# Digital_Output.net
KiCad netlist of a schematic drawn in Altium Designer
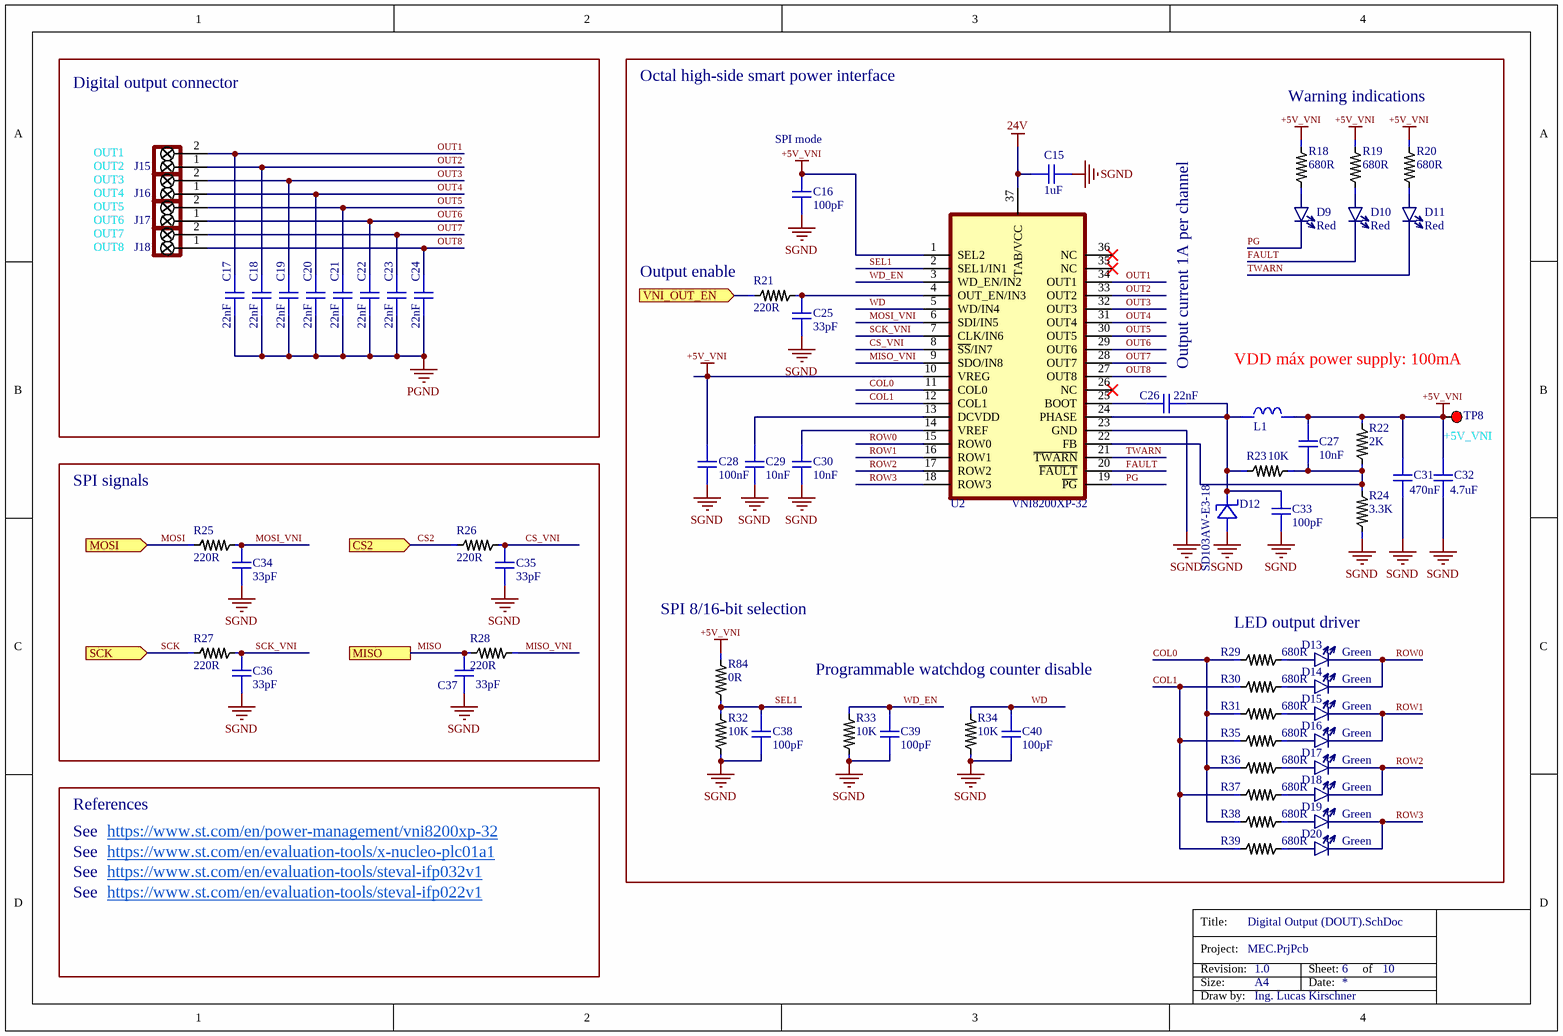
[diagram p0: Digital Output (DOUT).SchDoc]

(export (version "E")
  (design (tool "Eeschema 10.0.6"))
  (components
    (comp (ref "C15")
      (value "1uF")
      (footprint "CAPC1005N")
      (description "Multilayer Ceramic Capacitors MLCC - SMD/SMT 50V 1uF X5R 0402 10% HI CV")
      (fields (field (name "PART NUMBER") "CC0402KRX5R9BB105") (field (name "MANUFACTURER") "YAGEO"))
      (libsource (lib "SchLib") (part "C-MLCC-1uF-50V-10%-0402"))
    )
    (comp (ref "C16")
      (value "100pF")
      (footprint "CAPC1005N")
      (description "Multilayer Ceramic Capacitors MLCC - SMD/SMT 50 V 100pF X7R 0402 10%")
      (fields (field (name "PART NUMBER") "CC0402KRX7R9BB101") (field (name "MANUFACTURER") "YAGEO"))
      (libsource (lib "SchLib") (part "C-MLCC-100pF-50V-10%-0402"))
    )
    (comp (ref "C17")
      (value "22nF")
      (footprint "CAPC2012N")
      (description "Multilayer Ceramic Capacitors MLCC - SMD/SMT 100 V 0.022 uF X7R 0805 10%")
      (fields (field (name "PART NUMBER") "CC0805KRX7R0BB223") (field (name "MANUFACTURER") "YAGEO"))
      (libsource (lib "SchLib") (part "C-MLCC-22nF-100V-10%-0805"))
    )
    (comp (ref "C18")
      (value "22nF")
      (footprint "CAPC2012N")
      (description "Multilayer Ceramic Capacitors MLCC - SMD/SMT 100 V 0.022 uF X7R 0805 10%")
      (fields (field (name "PART NUMBER") "CC0805KRX7R0BB223") (field (name "MANUFACTURER") "YAGEO"))
      (libsource (lib "SchLib") (part "C-MLCC-22nF-100V-10%-0805"))
    )
    (comp (ref "C19")
      (value "22nF")
      (footprint "CAPC2012N")
      (description "Multilayer Ceramic Capacitors MLCC - SMD/SMT 100 V 0.022 uF X7R 0805 10%")
      (fields (field (name "PART NUMBER") "CC0805KRX7R0BB223") (field (name "MANUFACTURER") "YAGEO"))
      (libsource (lib "SchLib") (part "C-MLCC-22nF-100V-10%-0805"))
    )
    (comp (ref "C20")
      (value "22nF")
      (footprint "CAPC2012N")
      (description "Multilayer Ceramic Capacitors MLCC - SMD/SMT 100 V 0.022 uF X7R 0805 10%")
      (fields (field (name "PART NUMBER") "CC0805KRX7R0BB223") (field (name "MANUFACTURER") "YAGEO"))
      (libsource (lib "SchLib") (part "C-MLCC-22nF-100V-10%-0805"))
    )
    (comp (ref "C21")
      (value "22nF")
      (footprint "CAPC2012N")
      (description "Multilayer Ceramic Capacitors MLCC - SMD/SMT 100 V 0.022 uF X7R 0805 10%")
      (fields (field (name "PART NUMBER") "CC0805KRX7R0BB223") (field (name "MANUFACTURER") "YAGEO"))
      (libsource (lib "SchLib") (part "C-MLCC-22nF-100V-10%-0805"))
    )
    (comp (ref "C22")
      (value "22nF")
      (footprint "CAPC2012N")
      (description "Multilayer Ceramic Capacitors MLCC - SMD/SMT 100 V 0.022 uF X7R 0805 10%")
      (fields (field (name "PART NUMBER") "CC0805KRX7R0BB223") (field (name "MANUFACTURER") "YAGEO"))
      (libsource (lib "SchLib") (part "C-MLCC-22nF-100V-10%-0805"))
    )
    (comp (ref "C23")
      (value "22nF")
      (footprint "CAPC2012N")
      (description "Multilayer Ceramic Capacitors MLCC - SMD/SMT 100 V 0.022 uF X7R 0805 10%")
      (fields (field (name "PART NUMBER") "CC0805KRX7R0BB223") (field (name "MANUFACTURER") "YAGEO"))
      (libsource (lib "SchLib") (part "C-MLCC-22nF-100V-10%-0805"))
    )
    (comp (ref "C24")
      (value "22nF")
      (footprint "CAPC2012N")
      (description "Multilayer Ceramic Capacitors MLCC - SMD/SMT 100 V 0.022 uF X7R 0805 10%")
      (fields (field (name "PART NUMBER") "CC0805KRX7R0BB223") (field (name "MANUFACTURER") "YAGEO"))
      (libsource (lib "SchLib") (part "C-MLCC-22nF-100V-10%-0805"))
    )
    (comp (ref "C25")
      (value "33pF")
      (footprint "CAPC1005N")
      (description "Multilayer Ceramic Capacitors MLCC - SMD/SMT 50 V 33 pF C0G 0402 1%")
      (fields (field (name "PART NUMBER") "CC0402KRNPO9BN330") (field (name "MANUFACTURER") "YAGEO"))
      (libsource (lib "SchLib") (part "C-MLCC-33pF-50V-10%-0402"))
    )
    (comp (ref "C26")
      (value "22nF")
      (footprint "CAPC1005N")
      (description "Multilayer Ceramic Capacitors MLCC - SMD/SMT 50 V 0.022uF X7R 0402 10%")
      (fields (field (name "PART NUMBER") "CC0402KRX7R9BB223") (field (name "MANUFACTURER") "YAGEO"))
      (libsource (lib "SchLib") (part "C-MLCC-22nF-50V-10%-0402"))
    )
    (comp (ref "C27")
      (value "10nF")
      (footprint "CAPC1005N")
      (description "Multilayer Ceramic Capacitors MLCC - SMD/SMT 50 V 0.01uF X7R 0402 10%")
      (fields (field (name "PART NUMBER") "CC0402KRX7R9BB103") (field (name "MANUFACTURER") "YAGEO"))
      (libsource (lib "SchLib") (part "C-MLCC-10nF-50V-10%-0402"))
    )
    (comp (ref "C28")
      (value "100nF")
      (footprint "CAPC1005N")
      (description "Multilayer Ceramic Capacitors MLCC - SMD/SMT 50 V 0.1uF X7R 0402 10%")
      (fields (field (name "PART NUMBER") "CC0402KRX5R9BB104") (field (name "MANUFACTURER") "YAGEO"))
      (libsource (lib "SchLib") (part "C-MLCC-100nF-50V-10%-0402"))
    )
    (comp (ref "C29")
      (value "10nF")
      (footprint "CAPC1005N")
      (description "Multilayer Ceramic Capacitors MLCC - SMD/SMT 50 V 0.01uF X7R 0402 10%")
      (fields (field (name "PART NUMBER") "CC0402KRX7R9BB103") (field (name "MANUFACTURER") "YAGEO"))
      (libsource (lib "SchLib") (part "C-MLCC-10nF-50V-10%-0402"))
    )
    (comp (ref "C30")
      (value "10nF")
      (footprint "CAPC1005N")
      (description "Multilayer Ceramic Capacitors MLCC - SMD/SMT 50 V 0.01uF X7R 0402 10%")
      (fields (field (name "PART NUMBER") "CC0402KRX7R9BB103") (field (name "MANUFACTURER") "YAGEO"))
      (libsource (lib "SchLib") (part "C-MLCC-10nF-50V-10%-0402"))
    )
    (comp (ref "C31")
      (value "470nF")
      (footprint "CAPC1005N")
      (description "Multilayer Ceramic Capacitors MLCC - SMD/SMT 50 V 0.470uF X7R 0402 10%")
      (fields (field (name "PART NUMBER") "CC0402KRX5R9BB474") (field (name "MANUFACTURER") "YAGEO"))
      (libsource (lib "SchLib") (part "C-MLCC-470nF-50V-10%-0402"))
    )
    (comp (ref "C32")
      (value "4.7uF")
      (footprint "CAPC1005N")
      (description "Multilayer Ceramic Capacitors MLCC - SMD/SMT 10V 4.7uF X5R 0402 10% HI CV")
      (fields (field (name "PART NUMBER") "CC0402KRX5R6BB475") (field (name "MANUFACTURER") "YAGEO"))
      (libsource (lib "SchLib") (part "C-MLCC-4.7uF-10V-10%-0402"))
    )
    (comp (ref "C33")
      (value "100pF")
      (footprint "CAPC1005N")
      (description "Multilayer Ceramic Capacitors MLCC - SMD/SMT 50 V 100pF X7R 0402 10%")
      (fields (field (name "PART NUMBER") "CC0402KRX7R9BB101") (field (name "MANUFACTURER") "YAGEO"))
      (libsource (lib "SchLib") (part "C-MLCC-100pF-50V-10%-0402"))
    )
    (comp (ref "C34")
      (value "33pF")
      (footprint "CAPC1005N")
      (description "Multilayer Ceramic Capacitors MLCC - SMD/SMT 50 V 33 pF C0G 0402 1%")
      (fields (field (name "PART NUMBER") "CC0402KRNPO9BN330") (field (name "MANUFACTURER") "YAGEO"))
      (libsource (lib "SchLib") (part "C-MLCC-33pF-50V-10%-0402"))
    )
    (comp (ref "C35")
      (value "33pF")
      (footprint "CAPC1005N")
      (description "Multilayer Ceramic Capacitors MLCC - SMD/SMT 50 V 33 pF C0G 0402 1%")
      (fields (field (name "PART NUMBER") "CC0402KRNPO9BN330") (field (name "MANUFACTURER") "YAGEO"))
      (libsource (lib "SchLib") (part "C-MLCC-33pF-50V-10%-0402"))
    )
    (comp (ref "C36")
      (value "33pF")
      (footprint "CAPC1005N")
      (description "Multilayer Ceramic Capacitors MLCC - SMD/SMT 50 V 33 pF C0G 0402 1%")
      (fields (field (name "PART NUMBER") "CC0402KRNPO9BN330") (field (name "MANUFACTURER") "YAGEO"))
      (libsource (lib "SchLib") (part "C-MLCC-33pF-50V-10%-0402"))
    )
    (comp (ref "C37")
      (value "33pF")
      (footprint "CAPC1005N")
      (description "Multilayer Ceramic Capacitors MLCC - SMD/SMT 50 V 33 pF C0G 0402 1%")
      (fields (field (name "PART NUMBER") "CC0402KRNPO9BN330") (field (name "MANUFACTURER") "YAGEO"))
      (libsource (lib "SchLib") (part "C-MLCC-33pF-50V-10%-0402"))
    )
    (comp (ref "C38")
      (value "100pF")
      (footprint "CAPC1005N")
      (description "Multilayer Ceramic Capacitors MLCC - SMD/SMT 50 V 100pF X7R 0402 10%")
      (fields (field (name "PART NUMBER") "CC0402KRX7R9BB101") (field (name "MANUFACTURER") "YAGEO"))
      (libsource (lib "SchLib") (part "C-MLCC-100pF-50V-10%-0402"))
    )
    (comp (ref "C39")
      (value "100pF")
      (footprint "CAPC1005N")
      (description "Multilayer Ceramic Capacitors MLCC - SMD/SMT 50 V 100pF X7R 0402 10%")
      (fields (field (name "PART NUMBER") "CC0402KRX7R9BB101") (field (name "MANUFACTURER") "YAGEO"))
      (libsource (lib "SchLib") (part "C-MLCC-100pF-50V-10%-0402"))
    )
    (comp (ref "C40")
      (value "100pF")
      (footprint "CAPC1005N")
      (description "Multilayer Ceramic Capacitors MLCC - SMD/SMT 50 V 100pF X7R 0402 10%")
      (fields (field (name "PART NUMBER") "CC0402KRX7R9BB101") (field (name "MANUFACTURER") "YAGEO"))
      (libsource (lib "SchLib") (part "C-MLCC-100pF-50V-10%-0402"))
    )
    (comp (ref "D9")
      (value "Red")
      (footprint "LEDC1608X80N_RED")
      (description "Standard Single Color LEDs 0603 Red")
      (fields (field (name "PART NUMBER") "LTST-C190KRKT") (field (name "MANUFACTURER") "LITEON"))
      (libsource (lib "SchLib") (part "D-LED-RED-2V-20mA-0603"))
    )
    (comp (ref "D10")
      (value "Red")
      (footprint "LEDC1608X80N_RED")
      (description "Standard Single Color LEDs 0603 Red")
      (fields (field (name "PART NUMBER") "LTST-C190KRKT") (field (name "MANUFACTURER") "LITEON"))
      (libsource (lib "SchLib") (part "D-LED-RED-2V-20mA-0603"))
    )
    (comp (ref "D11")
      (value "Red")
      (footprint "LEDC1608X80N_RED")
      (description "Standard Single Color LEDs 0603 Red")
      (fields (field (name "PART NUMBER") "LTST-C190KRKT") (field (name "MANUFACTURER") "LITEON"))
      (libsource (lib "SchLib") (part "D-LED-RED-2V-20mA-0603"))
    )
    (comp (ref "D12")
      (value "Schottky Diodes")
      (footprint "SOD3705X110-2N")
      (description "Schottky Diodes & Rectifiers 350mA 40V SOD123")
      (fields
        (field (name "MANUFACTURER") "Vishay Semiconductors")
        (field (name "MOUSER PART #") "78-SD103AW-E3-18")
        (field (name "PART NUMBER") "SD103AW-E3-18")
      )
      (libsource (lib "SchLib") (part "D-SCH-350mA-40V-SOD123"))
    )
    (comp (ref "D13")
      (value "Green")
      (footprint "LEDC1608X80N_GREEN")
      (description "Standard Single Color LEDs 0603 Green")
      (fields (field (name "PART NUMBER") "LTST-C190KGKT") (field (name "MANUFACTURER") "LITEON"))
      (libsource (lib "SchLib") (part "D-LED-GREEN-2V-20mA-0603"))
    )
    (comp (ref "D14")
      (value "Green")
      (footprint "LEDC1608X80N_GREEN")
      (description "Standard Single Color LEDs 0603 Green")
      (fields (field (name "PART NUMBER") "LTST-C190KGKT") (field (name "MANUFACTURER") "LITEON"))
      (libsource (lib "SchLib") (part "D-LED-GREEN-2V-20mA-0603"))
    )
    (comp (ref "D15")
      (value "Green")
      (footprint "LEDC1608X80N_GREEN")
      (description "Standard Single Color LEDs 0603 Green")
      (fields (field (name "PART NUMBER") "LTST-C190KGKT") (field (name "MANUFACTURER") "LITEON"))
      (libsource (lib "SchLib") (part "D-LED-GREEN-2V-20mA-0603"))
    )
    (comp (ref "D16")
      (value "Green")
      (footprint "LEDC1608X80N_GREEN")
      (description "Standard Single Color LEDs 0603 Green")
      (fields (field (name "PART NUMBER") "LTST-C190KGKT") (field (name "MANUFACTURER") "LITEON"))
      (libsource (lib "SchLib") (part "D-LED-GREEN-2V-20mA-0603"))
    )
    (comp (ref "D17")
      (value "Green")
      (footprint "LEDC1608X80N_GREEN")
      (description "Standard Single Color LEDs 0603 Green")
      (fields (field (name "PART NUMBER") "LTST-C190KGKT") (field (name "MANUFACTURER") "LITEON"))
      (libsource (lib "SchLib") (part "D-LED-GREEN-2V-20mA-0603"))
    )
    (comp (ref "D18")
      (value "Green")
      (footprint "LEDC1608X80N_GREEN")
      (description "Standard Single Color LEDs 0603 Green")
      (fields (field (name "PART NUMBER") "LTST-C190KGKT") (field (name "MANUFACTURER") "LITEON"))
      (libsource (lib "SchLib") (part "D-LED-GREEN-2V-20mA-0603"))
    )
    (comp (ref "D19")
      (value "Green")
      (footprint "LEDC1608X80N_GREEN")
      (description "Standard Single Color LEDs 0603 Green")
      (fields (field (name "PART NUMBER") "LTST-C190KGKT") (field (name "MANUFACTURER") "LITEON"))
      (libsource (lib "SchLib") (part "D-LED-GREEN-2V-20mA-0603"))
    )
    (comp (ref "D20")
      (value "Green")
      (footprint "LEDC1608X80N_GREEN")
      (description "Standard Single Color LEDs 0603 Green")
      (fields (field (name "PART NUMBER") "LTST-C190KGKT") (field (name "MANUFACTURER") "LITEON"))
      (libsource (lib "SchLib") (part "D-LED-GREEN-2V-20mA-0603"))
    )
    (comp (ref "J15")
      (value "Terminal Blocks")
      (footprint "CONB_FIX508P-2N")
      (description "Pluggable Terminal Blocks 2 Pos 5.08mm pitch Through Hole Header")
      (fields (field (name "MOUSER PART #") "737-EBA-02-D-BU-01") (field (name "MANUFACTURER") "Adam Tech"))
      (libsource (lib "SchLib") (part "J-02-5P08-TERM-F-VERT-TH"))
    )
    (comp (ref "J16")
      (value "Terminal Blocks")
      (footprint "CONB_FIX508P-2N")
      (description "Pluggable Terminal Blocks 2 Pos 5.08mm pitch Through Hole Header")
      (fields (field (name "MOUSER PART #") "737-EBA-02-D-BU-01") (field (name "MANUFACTURER") "Adam Tech"))
      (libsource (lib "SchLib") (part "J-02-5P08-TERM-F-VERT-TH"))
    )
    (comp (ref "J17")
      (value "Terminal Blocks")
      (footprint "CONB_FIX508P-2N")
      (description "Pluggable Terminal Blocks 2 Pos 5.08mm pitch Through Hole Header")
      (fields (field (name "MOUSER PART #") "737-EBA-02-D-BU-01") (field (name "MANUFACTURER") "Adam Tech"))
      (libsource (lib "SchLib") (part "J-02-5P08-TERM-F-VERT-TH"))
    )
    (comp (ref "J18")
      (value "Terminal Blocks")
      (footprint "CONB_FIX508P-2N")
      (description "Pluggable Terminal Blocks 2 Pos 5.08mm pitch Through Hole Header")
      (fields (field (name "MOUSER PART #") "737-EBA-02-D-BU-01") (field (name "MANUFACTURER") "Adam Tech"))
      (libsource (lib "SchLib") (part "J-02-5P08-TERM-F-VERT-TH"))
    )
    (comp (ref "L1")
      (value "Power Inductor")
      (footprint "INDP4018220N")
      (description "Power Inductors - SMD 100uH 0.42A 1.6Ohms")
      (fields (field (name "MANUFACTURER") "Bourns") (field (name "PART NUMBER") "SRN4018-101M"))
      (libsource (lib "SchLib") (part "L-PWR-100uH-0.42A-SMT"))
    )
    (comp (ref "R18")
      (value "680R")
      (footprint "RESC1005N")
      (description "Thick Film Resistors - SMD General Purpose Chip Resistor 0402, 680Ohms, 1%, 1/16W")
      (fields (field (name "PART NUMBER") "RC0402FR-07680RL") (field (name "MANUFACTURER") "YAGEO"))
      (libsource (lib "SchLib") (part "R-THICK-680R-62.5mW-1%-0402"))
    )
    (comp (ref "R19")
      (value "680R")
      (footprint "RESC1005N")
      (description "Thick Film Resistors - SMD General Purpose Chip Resistor 0402, 680Ohms, 1%, 1/16W")
      (fields (field (name "PART NUMBER") "RC0402FR-07680RL") (field (name "MANUFACTURER") "YAGEO"))
      (libsource (lib "SchLib") (part "R-THICK-680R-62.5mW-1%-0402"))
    )
    (comp (ref "R20")
      (value "680R")
      (footprint "RESC1005N")
      (description "Thick Film Resistors - SMD General Purpose Chip Resistor 0402, 680Ohms, 1%, 1/16W")
      (fields (field (name "PART NUMBER") "RC0402FR-07680RL") (field (name "MANUFACTURER") "YAGEO"))
      (libsource (lib "SchLib") (part "R-THICK-680R-62.5mW-1%-0402"))
    )
    (comp (ref "R21")
      (value "220R")
      (footprint "RESC1005N")
      (description "Thick Film Resistors - SMD General Purpose Chip Resistor 0402, 220Ohms, 1%, 1/16W")
      (fields (field (name "PART NUMBER") "RC0402FR-07220RL") (field (name "MANUFACTURER") "YAGEO"))
      (libsource (lib "SchLib") (part "R-THICK-220R-62.5mW-1%-0402"))
    )
    (comp (ref "R22")
      (value "2K")
      (footprint "RESC1608N")
      (description "Thick Film Resistors - SMD General Purpose Chip Resistor 0603, 2kOhms, 1%, 1/10W")
      (fields (field (name "PART NUMBER") "RC0603FR-072KL") (field (name "MANUFACTURER") "YAGEO"))
      (libsource (lib "SchLib") (part "R-THICK-2K-100mW-1%-0603"))
    )
    (comp (ref "R23")
      (value "10K")
      (footprint "RESC1608N")
      (description "Thick Film Resistors - SMD General Purpose Chip Resistor 0603, 10kOhms, 1%, 1/10W")
      (fields (field (name "PART NUMBER") "RC0603FR-0710KL") (field (name "MANUFACTURER") "YAGEO"))
      (libsource (lib "SchLib") (part "R-THICK-10K-100mW-1%-0603"))
    )
    (comp (ref "R24")
      (value "3.3K")
      (footprint "RESC1608N")
      (description "Thick Film Resistors - SMD General Purpose Chip Resistor 0603, 3.3kOhms, 1%, 1/10W")
      (fields (field (name "PART NUMBER") "RC0603FR-073K3L") (field (name "MANUFACTURER") "YAGEO"))
      (libsource (lib "SchLib") (part "R-THICK-3K3-100mW-1%-0603"))
    )
    (comp (ref "R25")
      (value "220R")
      (footprint "RESC1005N")
      (description "Thick Film Resistors - SMD General Purpose Chip Resistor 0402, 220Ohms, 1%, 1/16W")
      (fields (field (name "PART NUMBER") "RC0402FR-07220RL") (field (name "MANUFACTURER") "YAGEO"))
      (libsource (lib "SchLib") (part "R-THICK-220R-62.5mW-1%-0402"))
    )
    (comp (ref "R26")
      (value "220R")
      (footprint "RESC1005N")
      (description "Thick Film Resistors - SMD General Purpose Chip Resistor 0402, 220Ohms, 1%, 1/16W")
      (fields (field (name "PART NUMBER") "RC0402FR-07220RL") (field (name "MANUFACTURER") "YAGEO"))
      (libsource (lib "SchLib") (part "R-THICK-220R-62.5mW-1%-0402"))
    )
    (comp (ref "R27")
      (value "220R")
      (footprint "RESC1005N")
      (description "Thick Film Resistors - SMD General Purpose Chip Resistor 0402, 220Ohms, 1%, 1/16W")
      (fields (field (name "PART NUMBER") "RC0402FR-07220RL") (field (name "MANUFACTURER") "YAGEO"))
      (libsource (lib "SchLib") (part "R-THICK-220R-62.5mW-1%-0402"))
    )
    (comp (ref "R28")
      (value "220R")
      (footprint "RESC1005N")
      (description "Thick Film Resistors - SMD General Purpose Chip Resistor 0402, 220Ohms, 1%, 1/16W")
      (fields (field (name "PART NUMBER") "RC0402FR-07220RL") (field (name "MANUFACTURER") "YAGEO"))
      (libsource (lib "SchLib") (part "R-THICK-220R-62.5mW-1%-0402"))
    )
    (comp (ref "R29")
      (value "680R")
      (footprint "RESC1005N")
      (description "Thick Film Resistors - SMD General Purpose Chip Resistor 0402, 680Ohms, 1%, 1/16W")
      (fields (field (name "PART NUMBER") "RC0402FR-07680RL") (field (name "MANUFACTURER") "YAGEO"))
      (libsource (lib "SchLib") (part "R-THICK-680R-62.5mW-1%-0402"))
    )
    (comp (ref "R30")
      (value "680R")
      (footprint "RESC1005N")
      (description "Thick Film Resistors - SMD General Purpose Chip Resistor 0402, 680Ohms, 1%, 1/16W")
      (fields (field (name "PART NUMBER") "RC0402FR-07680RL") (field (name "MANUFACTURER") "YAGEO"))
      (libsource (lib "SchLib") (part "R-THICK-680R-62.5mW-1%-0402"))
    )
    (comp (ref "R31")
      (value "680R")
      (footprint "RESC1005N")
      (description "Thick Film Resistors - SMD General Purpose Chip Resistor 0402, 680Ohms, 1%, 1/16W")
      (fields (field (name "PART NUMBER") "RC0402FR-07680RL") (field (name "MANUFACTURER") "YAGEO"))
      (libsource (lib "SchLib") (part "R-THICK-680R-62.5mW-1%-0402"))
    )
    (comp (ref "R32")
      (value "10K")
      (footprint "RESC1005N")
      (description "Thick Film Resistors - SMD General Purpose Chip Resistor 0402, 10kOhms, 1%, 1/16W")
      (fields (field (name "PART NUMBER") "RC0402FR-0710KL") (field (name "MANUFACTURER") "YAGEO"))
      (libsource (lib "SchLib") (part "R-THICK-10K-62.5mW-1%-0402"))
    )
    (comp (ref "R33")
      (value "10K")
      (footprint "RESC1005N")
      (description "Thick Film Resistors - SMD General Purpose Chip Resistor 0402, 10kOhms, 1%, 1/16W")
      (fields (field (name "PART NUMBER") "RC0402FR-0710KL") (field (name "MANUFACTURER") "YAGEO"))
      (libsource (lib "SchLib") (part "R-THICK-10K-62.5mW-1%-0402"))
    )
    (comp (ref "R34")
      (value "10K")
      (footprint "RESC1005N")
      (description "Thick Film Resistors - SMD General Purpose Chip Resistor 0402, 10kOhms, 1%, 1/16W")
      (fields (field (name "PART NUMBER") "RC0402FR-0710KL") (field (name "MANUFACTURER") "YAGEO"))
      (libsource (lib "SchLib") (part "R-THICK-10K-62.5mW-1%-0402"))
    )
    (comp (ref "R35")
      (value "680R")
      (footprint "RESC1005N")
      (description "Thick Film Resistors - SMD General Purpose Chip Resistor 0402, 680Ohms, 1%, 1/16W")
      (fields (field (name "PART NUMBER") "RC0402FR-07680RL") (field (name "MANUFACTURER") "YAGEO"))
      (libsource (lib "SchLib") (part "R-THICK-680R-62.5mW-1%-0402"))
    )
    (comp (ref "R36")
      (value "680R")
      (footprint "RESC1005N")
      (description "Thick Film Resistors - SMD General Purpose Chip Resistor 0402, 680Ohms, 1%, 1/16W")
      (fields (field (name "PART NUMBER") "RC0402FR-07680RL") (field (name "MANUFACTURER") "YAGEO"))
      (libsource (lib "SchLib") (part "R-THICK-680R-62.5mW-1%-0402"))
    )
    (comp (ref "R37")
      (value "680R")
      (footprint "RESC1005N")
      (description "Thick Film Resistors - SMD General Purpose Chip Resistor 0402, 680Ohms, 1%, 1/16W")
      (fields (field (name "PART NUMBER") "RC0402FR-07680RL") (field (name "MANUFACTURER") "YAGEO"))
      (libsource (lib "SchLib") (part "R-THICK-680R-62.5mW-1%-0402"))
    )
    (comp (ref "R38")
      (value "680R")
      (footprint "RESC1005N")
      (description "Thick Film Resistors - SMD General Purpose Chip Resistor 0402, 680Ohms, 1%, 1/16W")
      (fields (field (name "PART NUMBER") "RC0402FR-07680RL") (field (name "MANUFACTURER") "YAGEO"))
      (libsource (lib "SchLib") (part "R-THICK-680R-62.5mW-1%-0402"))
    )
    (comp (ref "R39")
      (value "680R")
      (footprint "RESC1005N")
      (description "Thick Film Resistors - SMD General Purpose Chip Resistor 0402, 680Ohms, 1%, 1/16W")
      (fields (field (name "PART NUMBER") "RC0402FR-07680RL") (field (name "MANUFACTURER") "YAGEO"))
      (libsource (lib "SchLib") (part "R-THICK-680R-62.5mW-1%-0402"))
    )
    (comp (ref "R84")
      (value "0R")
      (footprint "RESC1005N")
      (description "Thick Film Resistors - SMD General Purpose Chip Resistor 0402, 0Ohms, 1%, 1/16W")
      (fields (field (name "PART NUMBER") "RC0402FR-070RL") (field (name "MANUFACTURER") "YAGEO"))
      (libsource (lib "SchLib") (part "R-THICK-0R-62.5mW-1%-0402"))
    )
    (comp (ref "TP8")
      (value "Test point")
      (footprint "TP-1MM")
      (description "Test point, 1mm, exposed pad")
      (fields (field (name "JLCPCB PART #") "C5199810"))
      (libsource (lib "SchLib") (part "TP-1MM-SMD"))
    )
    (comp (ref "U2")
      (value "Power Switch ICs")
      (footprint "SOP50P1030X245-37N")
      (description "Power Switch ICs - Power Distribution 8-Ch Octal HS SSR 100mA VIPower")
      (fields
        (field (name "MANUFACTURER") "STMicroelectronics")
        (field (name "MOUSER PART #") "511-VNI8200XP-32")
        (field (name "PART NUMBER") "VNI8200XP-32")
      )
      (libsource (lib "SchLib") (part "U-VNI8200XP-32"))
    )
  )
  (nets
    (net (code "1") (name "+5V_VNI") (class "Default")
      (node (ref "C16") (pin "1") (pinfunction "1_1") (pintype "passive"))
      (node (ref "C27") (pin "1") (pinfunction "1_1") (pintype "passive"))
      (node (ref "C28") (pin "1") (pinfunction "1_1") (pintype "passive"))
      (node (ref "C31") (pin "1") (pinfunction "1_1") (pintype "passive"))
      (node (ref "C32") (pin "1") (pinfunction "1_1") (pintype "passive"))
      (node (ref "L1") (pin "2") (pinfunction "2_2") (pintype "passive"))
      (node (ref "R18") (pin "2") (pinfunction "2_2") (pintype "passive"))
      (node (ref "R19") (pin "2") (pinfunction "2_2") (pintype "passive"))
      (node (ref "R20") (pin "2") (pinfunction "2_2") (pintype "passive"))
      (node (ref "R22") (pin "2") (pinfunction "2_2") (pintype "passive"))
      (node (ref "R84") (pin "2") (pinfunction "2_2") (pintype "passive"))
      (node (ref "TP8") (pin "1") (pinfunction "1_1") (pintype "passive"))
      (node (ref "U2") (pin "1") (pinfunction "SEL2_1") (pintype "passive"))
      (node (ref "U2") (pin "10") (pinfunction "VREG_10") (pintype "passive"))
    )
    (net (code "2") (name "/COL0") (class "Default")
      (node (ref "R29") (pin "2") (pinfunction "2_2") (pintype "passive"))
      (node (ref "R31") (pin "2") (pinfunction "2_2") (pintype "passive"))
      (node (ref "R36") (pin "2") (pinfunction "2_2") (pintype "passive"))
      (node (ref "R38") (pin "2") (pinfunction "2_2") (pintype "passive"))
      (node (ref "U2") (pin "11") (pinfunction "COL0_11") (pintype "passive"))
    )
    (net (code "3") (name "/COL1") (class "Default")
      (node (ref "R30") (pin "2") (pinfunction "2_2") (pintype "passive"))
      (node (ref "R35") (pin "2") (pinfunction "2_2") (pintype "passive"))
      (node (ref "R37") (pin "2") (pinfunction "2_2") (pintype "passive"))
      (node (ref "R39") (pin "2") (pinfunction "2_2") (pintype "passive"))
      (node (ref "U2") (pin "12") (pinfunction "COL1_12") (pintype "passive"))
    )
    (net (code "4") (name "/CS2") (class "Default")
      (node (ref "R26") (pin "1") (pinfunction "1_1") (pintype "passive"))
    )
    (net (code "5") (name "/CS_VNI") (class "Default")
      (node (ref "C35") (pin "1") (pinfunction "1_1") (pintype "passive"))
      (node (ref "R26") (pin "2") (pinfunction "2_2") (pintype "passive"))
      (node (ref "U2") (pin "8") (pinfunction "~{SS}/IN7_8") (pintype "passive"))
    )
    (net (code "6") (name "/FAULT") (class "Default")
      (node (ref "D10") (pin "C") (pinfunction "C_C") (pintype "passive"))
      (node (ref "U2") (pin "20") (pinfunction "~{FAULT}_20") (pintype "passive"))
    )
    (net (code "7") (name "/MISO") (class "Default")
      (node (ref "C37") (pin "1") (pinfunction "1_1") (pintype "passive"))
      (node (ref "R28") (pin "1") (pinfunction "1_1") (pintype "passive"))
    )
    (net (code "8") (name "/MISO_VNI") (class "Default")
      (node (ref "R28") (pin "2") (pinfunction "2_2") (pintype "passive"))
      (node (ref "U2") (pin "9") (pinfunction "SDO/IN8_9") (pintype "passive"))
    )
    (net (code "9") (name "/MOSI") (class "Default")
      (node (ref "R25") (pin "1") (pinfunction "1_1") (pintype "passive"))
    )
    (net (code "10") (name "/MOSI_VNI") (class "Default")
      (node (ref "C34") (pin "1") (pinfunction "1_1") (pintype "passive"))
      (node (ref "R25") (pin "2") (pinfunction "2_2") (pintype "passive"))
      (node (ref "U2") (pin "6") (pinfunction "SDI/IN5_6") (pintype "passive"))
    )
    (net (code "11") (name "/OUT1") (class "Default")
      (node (ref "C17") (pin "1") (pinfunction "1_1") (pintype "passive"))
      (node (ref "J15") (pin "2") (pinfunction "2_2") (pintype "passive"))
      (node (ref "U2") (pin "34") (pinfunction "OUT1_34") (pintype "passive"))
    )
    (net (code "12") (name "/OUT2") (class "Default")
      (node (ref "C18") (pin "1") (pinfunction "1_1") (pintype "passive"))
      (node (ref "J15") (pin "1") (pinfunction "1_1") (pintype "passive"))
      (node (ref "U2") (pin "33") (pinfunction "OUT2_33") (pintype "passive"))
    )
    (net (code "13") (name "/OUT3") (class "Default")
      (node (ref "C19") (pin "1") (pinfunction "1_1") (pintype "passive"))
      (node (ref "J16") (pin "2") (pinfunction "2_2") (pintype "passive"))
      (node (ref "U2") (pin "32") (pinfunction "OUT3_32") (pintype "passive"))
    )
    (net (code "14") (name "/OUT4") (class "Default")
      (node (ref "C20") (pin "1") (pinfunction "1_1") (pintype "passive"))
      (node (ref "J16") (pin "1") (pinfunction "1_1") (pintype "passive"))
      (node (ref "U2") (pin "31") (pinfunction "OUT4_31") (pintype "passive"))
    )
    (net (code "15") (name "/OUT5") (class "Default")
      (node (ref "C21") (pin "1") (pinfunction "1_1") (pintype "passive"))
      (node (ref "J17") (pin "2") (pinfunction "2_2") (pintype "passive"))
      (node (ref "U2") (pin "30") (pinfunction "OUT5_30") (pintype "passive"))
    )
    (net (code "16") (name "/OUT6") (class "Default")
      (node (ref "C22") (pin "1") (pinfunction "1_1") (pintype "passive"))
      (node (ref "J17") (pin "1") (pinfunction "1_1") (pintype "passive"))
      (node (ref "U2") (pin "29") (pinfunction "OUT6_29") (pintype "passive"))
    )
    (net (code "17") (name "/OUT7") (class "Default")
      (node (ref "C23") (pin "1") (pinfunction "1_1") (pintype "passive"))
      (node (ref "J18") (pin "2") (pinfunction "2_2") (pintype "passive"))
      (node (ref "U2") (pin "28") (pinfunction "OUT7_28") (pintype "passive"))
    )
    (net (code "18") (name "/OUT8") (class "Default")
      (node (ref "C24") (pin "1") (pinfunction "1_1") (pintype "passive"))
      (node (ref "J18") (pin "1") (pinfunction "1_1") (pintype "passive"))
      (node (ref "U2") (pin "27") (pinfunction "OUT8_27") (pintype "passive"))
    )
    (net (code "19") (name "/PG") (class "Default")
      (node (ref "D9") (pin "C") (pinfunction "C_C") (pintype "passive"))
      (node (ref "U2") (pin "19") (pinfunction "~{PG}_19") (pintype "passive"))
    )
    (net (code "20") (name "/ROW0") (class "Default")
      (node (ref "D13") (pin "C") (pinfunction "C_C") (pintype "passive"))
      (node (ref "D14") (pin "C") (pinfunction "C_C") (pintype "passive"))
      (node (ref "U2") (pin "15") (pinfunction "ROW0_15") (pintype "passive"))
    )
    (net (code "21") (name "/ROW1") (class "Default")
      (node (ref "D15") (pin "C") (pinfunction "C_C") (pintype "passive"))
      (node (ref "D16") (pin "C") (pinfunction "C_C") (pintype "passive"))
      (node (ref "U2") (pin "16") (pinfunction "ROW1_16") (pintype "passive"))
    )
    (net (code "22") (name "/ROW2") (class "Default")
      (node (ref "D17") (pin "C") (pinfunction "C_C") (pintype "passive"))
      (node (ref "D18") (pin "C") (pinfunction "C_C") (pintype "passive"))
      (node (ref "U2") (pin "17") (pinfunction "ROW2_17") (pintype "passive"))
    )
    (net (code "23") (name "/ROW3") (class "Default")
      (node (ref "D19") (pin "C") (pinfunction "C_C") (pintype "passive"))
      (node (ref "D20") (pin "C") (pinfunction "C_C") (pintype "passive"))
      (node (ref "U2") (pin "18") (pinfunction "ROW3_18") (pintype "passive"))
    )
    (net (code "24") (name "/SCK") (class "Default")
      (node (ref "R27") (pin "1") (pinfunction "1_1") (pintype "passive"))
    )
    (net (code "25") (name "/SCK_VNI") (class "Default")
      (node (ref "C36") (pin "1") (pinfunction "1_1") (pintype "passive"))
      (node (ref "R27") (pin "2") (pinfunction "2_2") (pintype "passive"))
      (node (ref "U2") (pin "7") (pinfunction "CLK/IN6_7") (pintype "passive"))
    )
    (net (code "26") (name "/SEL1") (class "Default")
      (node (ref "C38") (pin "1") (pinfunction "1_1") (pintype "passive"))
      (node (ref "R32") (pin "2") (pinfunction "2_2") (pintype "passive"))
      (node (ref "R84") (pin "1") (pinfunction "1_1") (pintype "passive"))
      (node (ref "U2") (pin "2") (pinfunction "SEL1/IN1_2") (pintype "passive"))
    )
    (net (code "27") (name "/TWARN") (class "Default")
      (node (ref "D11") (pin "C") (pinfunction "C_C") (pintype "passive"))
      (node (ref "U2") (pin "21") (pinfunction "~{TWARN}_21") (pintype "passive"))
    )
    (net (code "28") (name "/VNI_OUT_EN") (class "Default")
      (node (ref "R21") (pin "1") (pinfunction "1_1") (pintype "passive"))
    )
    (net (code "29") (name "/WD") (class "Default")
      (node (ref "C40") (pin "1") (pinfunction "1_1") (pintype "passive"))
      (node (ref "R34") (pin "2") (pinfunction "2_2") (pintype "passive"))
      (node (ref "U2") (pin "5") (pinfunction "WD/IN4_5") (pintype "passive"))
    )
    (net (code "30") (name "/WD_EN") (class "Default")
      (node (ref "C39") (pin "1") (pinfunction "1_1") (pintype "passive"))
      (node (ref "R33") (pin "2") (pinfunction "2_2") (pintype "passive"))
      (node (ref "U2") (pin "3") (pinfunction "WD_EN/IN2_3") (pintype "passive"))
    )
    (net (code "31") (name "24V") (class "Default")
      (node (ref "C15") (pin "1") (pinfunction "1_1") (pintype "passive"))
      (node (ref "U2") (pin "37") (pinfunction "TAB/VCC_37") (pintype "passive"))
    )
    (net (code "32") (name "Net-(D9-PadA)") (class "Default")
      (node (ref "D9") (pin "A") (pinfunction "A_A") (pintype "passive"))
      (node (ref "R18") (pin "1") (pinfunction "1_1") (pintype "passive"))
    )
    (net (code "33") (name "Net-(D10-PadA)") (class "Default")
      (node (ref "D10") (pin "A") (pinfunction "A_A") (pintype "passive"))
      (node (ref "R19") (pin "1") (pinfunction "1_1") (pintype "passive"))
    )
    (net (code "34") (name "Net-(D11-PadA)") (class "Default")
      (node (ref "D11") (pin "A") (pinfunction "A_A") (pintype "passive"))
      (node (ref "R20") (pin "1") (pinfunction "1_1") (pintype "passive"))
    )
    (net (code "35") (name "Net-(D13-PadA)") (class "Default")
      (node (ref "D13") (pin "A") (pinfunction "A_A") (pintype "passive"))
      (node (ref "R29") (pin "1") (pinfunction "1_1") (pintype "passive"))
    )
    (net (code "36") (name "Net-(D14-PadA)") (class "Default")
      (node (ref "D14") (pin "A") (pinfunction "A_A") (pintype "passive"))
      (node (ref "R30") (pin "1") (pinfunction "1_1") (pintype "passive"))
    )
    (net (code "37") (name "Net-(D15-PadA)") (class "Default")
      (node (ref "D15") (pin "A") (pinfunction "A_A") (pintype "passive"))
      (node (ref "R31") (pin "1") (pinfunction "1_1") (pintype "passive"))
    )
    (net (code "38") (name "Net-(D16-PadA)") (class "Default")
      (node (ref "D16") (pin "A") (pinfunction "A_A") (pintype "passive"))
      (node (ref "R35") (pin "1") (pinfunction "1_1") (pintype "passive"))
    )
    (net (code "39") (name "Net-(D17-PadA)") (class "Default")
      (node (ref "D17") (pin "A") (pinfunction "A_A") (pintype "passive"))
      (node (ref "R36") (pin "1") (pinfunction "1_1") (pintype "passive"))
    )
    (net (code "40") (name "Net-(D18-PadA)") (class "Default")
      (node (ref "D18") (pin "A") (pinfunction "A_A") (pintype "passive"))
      (node (ref "R37") (pin "1") (pinfunction "1_1") (pintype "passive"))
    )
    (net (code "41") (name "Net-(D19-PadA)") (class "Default")
      (node (ref "D19") (pin "A") (pinfunction "A_A") (pintype "passive"))
      (node (ref "R38") (pin "1") (pinfunction "1_1") (pintype "passive"))
    )
    (net (code "42") (name "Net-(D20-PadA)") (class "Default")
      (node (ref "D20") (pin "A") (pinfunction "A_A") (pintype "passive"))
      (node (ref "R39") (pin "1") (pinfunction "1_1") (pintype "passive"))
    )
    (net (code "43") (name "Net-(U2-BOOT)") (class "Default")
      (node (ref "C26") (pin "1") (pinfunction "1_1") (pintype "passive"))
      (node (ref "U2") (pin "25") (pinfunction "BOOT_25") (pintype "passive"))
    )
    (net (code "44") (name "Net-(U2-DCVDD)") (class "Default")
      (node (ref "C29") (pin "1") (pinfunction "1_1") (pintype "passive"))
      (node (ref "U2") (pin "13") (pinfunction "DCVDD_13") (pintype "passive"))
    )
    (net (code "45") (name "Net-(U2-FB)") (class "Default")
      (node (ref "C27") (pin "2") (pinfunction "2_2") (pintype "passive"))
      (node (ref "R22") (pin "1") (pinfunction "1_1") (pintype "passive"))
      (node (ref "R23") (pin "2") (pinfunction "2_2") (pintype "passive"))
      (node (ref "R24") (pin "2") (pinfunction "2_2") (pintype "passive"))
      (node (ref "U2") (pin "22") (pinfunction "FB_22") (pintype "passive"))
    )
    (net (code "46") (name "Net-(U2-OUT_EN{slash}IN3)") (class "Default")
      (node (ref "C25") (pin "1") (pinfunction "1_1") (pintype "passive"))
      (node (ref "R21") (pin "2") (pinfunction "2_2") (pintype "passive"))
      (node (ref "U2") (pin "4") (pinfunction "OUT_EN/IN3_4") (pintype "passive"))
    )
    (net (code "47") (name "Net-(U2-PHASE)") (class "Default")
      (node (ref "C26") (pin "2") (pinfunction "2_2") (pintype "passive"))
      (node (ref "C33") (pin "1") (pinfunction "1_1") (pintype "passive"))
      (node (ref "D12") (pin "C") (pinfunction "C_C") (pintype "passive"))
      (node (ref "L1") (pin "1") (pinfunction "1_1") (pintype "passive"))
      (node (ref "R23") (pin "1") (pinfunction "1_1") (pintype "passive"))
      (node (ref "U2") (pin "24") (pinfunction "PHASE_24") (pintype "passive"))
    )
    (net (code "48") (name "Net-(U2-VREF)") (class "Default")
      (node (ref "C30") (pin "1") (pinfunction "1_1") (pintype "passive"))
      (node (ref "U2") (pin "14") (pinfunction "VREF_14") (pintype "passive"))
    )
    (net (code "49") (name "PGND") (class "Default")
      (node (ref "C17") (pin "2") (pinfunction "2_2") (pintype "passive"))
      (node (ref "C18") (pin "2") (pinfunction "2_2") (pintype "passive"))
      (node (ref "C19") (pin "2") (pinfunction "2_2") (pintype "passive"))
      (node (ref "C20") (pin "2") (pinfunction "2_2") (pintype "passive"))
      (node (ref "C21") (pin "2") (pinfunction "2_2") (pintype "passive"))
      (node (ref "C22") (pin "2") (pinfunction "2_2") (pintype "passive"))
      (node (ref "C23") (pin "2") (pinfunction "2_2") (pintype "passive"))
      (node (ref "C24") (pin "2") (pinfunction "2_2") (pintype "passive"))
    )
    (net (code "50") (name "SGND") (class "Default")
      (node (ref "C15") (pin "2") (pinfunction "2_2") (pintype "passive"))
      (node (ref "C16") (pin "2") (pinfunction "2_2") (pintype "passive"))
      (node (ref "C25") (pin "2") (pinfunction "2_2") (pintype "passive"))
      (node (ref "C28") (pin "2") (pinfunction "2_2") (pintype "passive"))
      (node (ref "C29") (pin "2") (pinfunction "2_2") (pintype "passive"))
      (node (ref "C30") (pin "2") (pinfunction "2_2") (pintype "passive"))
      (node (ref "C31") (pin "2") (pinfunction "2_2") (pintype "passive"))
      (node (ref "C32") (pin "2") (pinfunction "2_2") (pintype "passive"))
      (node (ref "C33") (pin "2") (pinfunction "2_2") (pintype "passive"))
      (node (ref "C34") (pin "2") (pinfunction "2_2") (pintype "passive"))
      (node (ref "C35") (pin "2") (pinfunction "2_2") (pintype "passive"))
      (node (ref "C36") (pin "2") (pinfunction "2_2") (pintype "passive"))
      (node (ref "C37") (pin "2") (pinfunction "2_2") (pintype "passive"))
      (node (ref "C38") (pin "2") (pinfunction "2_2") (pintype "passive"))
      (node (ref "C39") (pin "2") (pinfunction "2_2") (pintype "passive"))
      (node (ref "C40") (pin "2") (pinfunction "2_2") (pintype "passive"))
      (node (ref "D12") (pin "A") (pinfunction "A_A") (pintype "passive"))
      (node (ref "R24") (pin "1") (pinfunction "1_1") (pintype "passive"))
      (node (ref "R32") (pin "1") (pinfunction "1_1") (pintype "passive"))
      (node (ref "R33") (pin "1") (pinfunction "1_1") (pintype "passive"))
      (node (ref "R34") (pin "1") (pinfunction "1_1") (pintype "passive"))
      (node (ref "U2") (pin "23") (pinfunction "GND_23") (pintype "passive"))
    )
    (net (code "51") (name "unconnected-(U2-NC-Pad26)") (class "Default")
      (node (ref "U2") (pin "26") (pinfunction "NC_26") (pintype "passive+no_connect"))
    )
    (net (code "52") (name "unconnected-(U2-NC-Pad35)") (class "Default")
      (node (ref "U2") (pin "35") (pinfunction "NC_35") (pintype "passive+no_connect"))
    )
    (net (code "53") (name "unconnected-(U2-NC-Pad36)") (class "Default")
      (node (ref "U2") (pin "36") (pinfunction "NC_36") (pintype "passive+no_connect"))
    )
  )
)
